# boost_phase.net
KiCad netlist of a schematic drawn in EAGLE
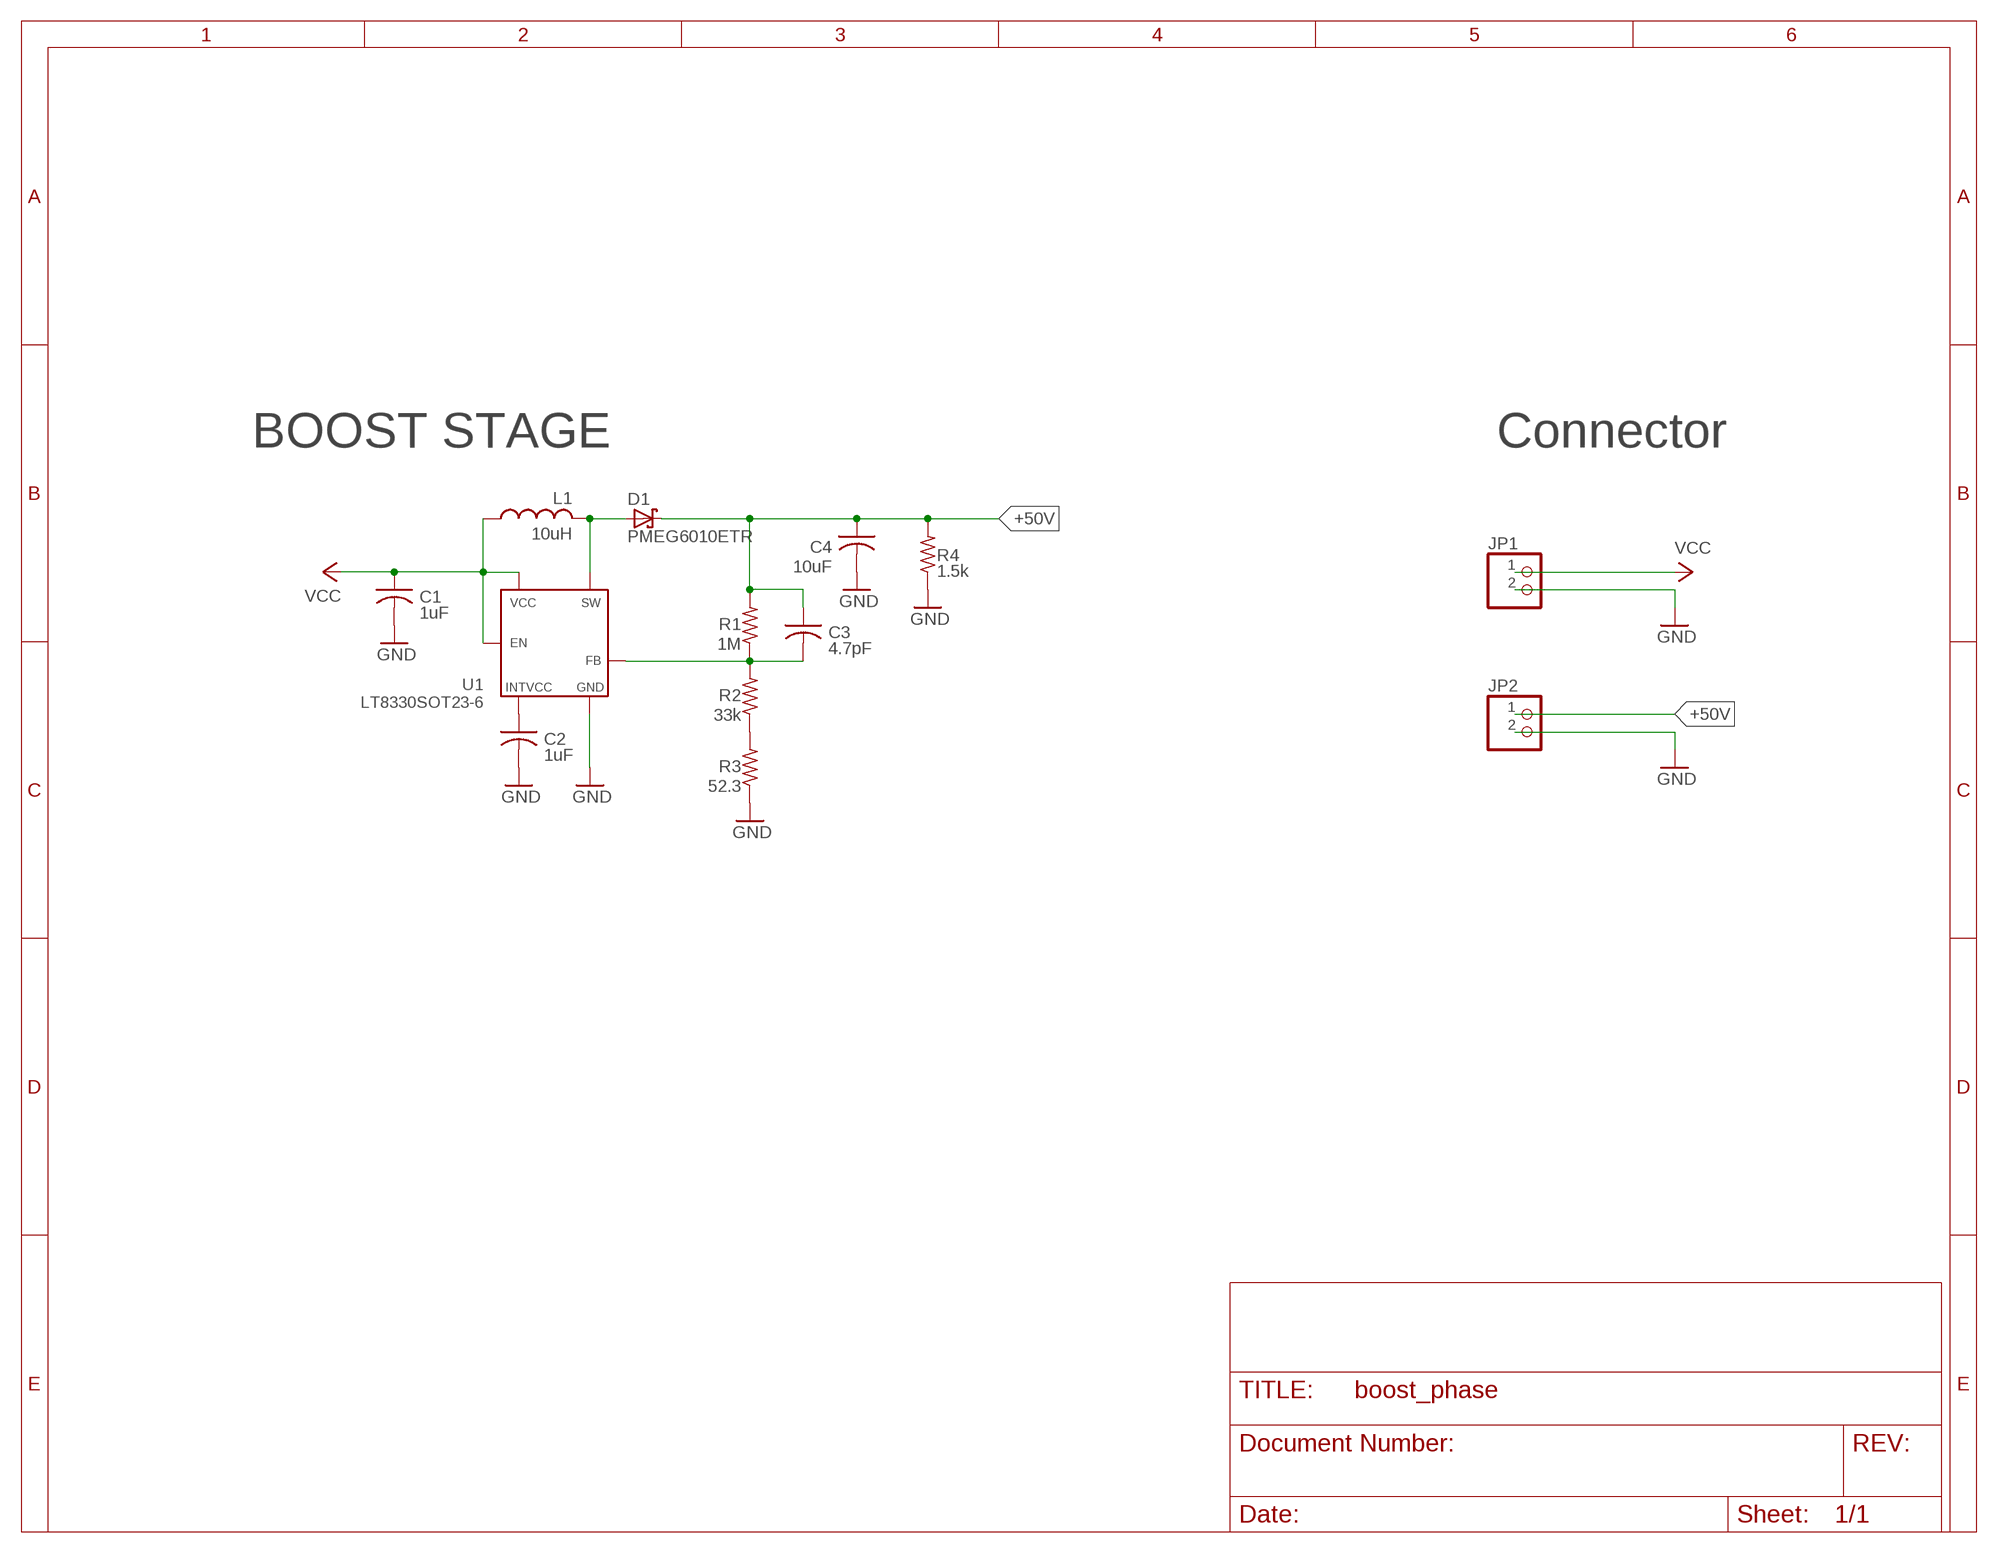
[diagram p0: schematic, sheet 1]

(export (version "E")
  (design (tool "Eeschema 10.0.6"))
  (components
    (comp (ref "C1")
      (value "1uF")
      (footprint "eagle-import:C0805")
      (libsource (lib "eagle-import") (part "C-USC0805"))
    )
    (comp (ref "C2")
      (value "1uF")
      (footprint "eagle-import:C0805")
      (libsource (lib "eagle-import") (part "C-USC0805"))
    )
    (comp (ref "C3")
      (value "4.7pF")
      (footprint "eagle-import:C0805")
      (libsource (lib "eagle-import") (part "C-USC0805"))
    )
    (comp (ref "C4")
      (value "10uF")
      (footprint "eagle-import:2J-LEAD")
      (libsource (lib "eagle-import") (part "CAPACITOR2-J-LEAD"))
    )
    (comp (ref "D1")
      (value "PMEG6010ETR")
      (footprint "eagle-import:SOD123")
      (libsource (lib "eagle-import") (part "SCHOTTKYSOD123"))
    )
    (comp (ref "JP1")
      (value "SCREWTERM_1X2")
      (footprint "eagle-import:SCREWTERM_1X2")
      (libsource (lib "eagle-import") (part "SCREWTERM_1X2"))
    )
    (comp (ref "JP2")
      (value "SCREWTERM_1X2")
      (footprint "eagle-import:SCREWTERM_1X2")
      (libsource (lib "eagle-import") (part "SCREWTERM_1X2"))
    )
    (comp (ref "L1")
      (value "10uH")
      (footprint "eagle-import:PQ2614")
      (libsource (lib "eagle-import") (part "INDUCTORPQ2614"))
    )
    (comp (ref "R1")
      (value "1M")
      (footprint "eagle-import:R0805")
      (libsource (lib "eagle-import") (part "R-US_R0805"))
    )
    (comp (ref "R2")
      (value "33k")
      (footprint "eagle-import:R0805")
      (libsource (lib "eagle-import") (part "R-US_R0805"))
    )
    (comp (ref "R3")
      (value "52.3")
      (footprint "eagle-import:R0805")
      (libsource (lib "eagle-import") (part "R-US_R0805"))
    )
    (comp (ref "R4")
      (value "1.5k")
      (footprint "eagle-import:R2512")
      (libsource (lib "eagle-import") (part "R-US_R2512"))
    )
    (comp (ref "U1")
      (value "LT8330SOT23-6")
      (footprint "eagle-import:SOT23-6")
      (libsource (lib "eagle-import") (part "LT8330SOT23-6"))
    )
  )
  (nets
    (net (code "1") (name "+50V") (class "Default")
      (node (ref "C3") (pin "1") (pinfunction "1_1") (pintype "passive"))
      (node (ref "C4") (pin "P$1") (pinfunction "1_P$1") (pintype "passive"))
      (node (ref "D1") (pin "P$2") (pinfunction "C_P$2") (pintype "passive"))
      (node (ref "JP2") (pin "1") (pinfunction "1_1") (pintype "passive"))
      (node (ref "R1") (pin "2") (pinfunction "2_2") (pintype "passive"))
      (node (ref "R4") (pin "2") (pinfunction "2_2") (pintype "passive"))
    )
    (net (code "2") (name "GND") (class "Default")
      (node (ref "C1") (pin "2") (pinfunction "2_2") (pintype "passive"))
      (node (ref "C2") (pin "2") (pinfunction "2_2") (pintype "passive"))
      (node (ref "C4") (pin "P$2") (pinfunction "2_P$2") (pintype "passive"))
      (node (ref "JP1") (pin "2") (pinfunction "2_2") (pintype "passive"))
      (node (ref "JP2") (pin "2") (pinfunction "2_2") (pintype "passive"))
      (node (ref "R3") (pin "1") (pinfunction "1_1") (pintype "passive"))
      (node (ref "R4") (pin "1") (pinfunction "1_1") (pintype "passive"))
      (node (ref "U1") (pin "2") (pinfunction "GND_2") (pintype "bidirectional"))
    )
    (net (code "3") (name "Net-(D1-A)") (class "Default")
      (node (ref "D1") (pin "P$1") (pinfunction "A_P$1") (pintype "passive"))
      (node (ref "L1") (pin "P$3") (pinfunction "2_P$3") (pintype "passive"))
      (node (ref "U1") (pin "1") (pinfunction "SW_1") (pintype "bidirectional"))
    )
    (net (code "4") (name "Net-(R2-Pad1)") (class "Default")
      (node (ref "R2") (pin "1") (pinfunction "1_1") (pintype "passive"))
      (node (ref "R3") (pin "2") (pinfunction "2_2") (pintype "passive"))
    )
    (net (code "5") (name "Net-(U1-FB)") (class "Default")
      (node (ref "C3") (pin "2") (pinfunction "2_2") (pintype "passive"))
      (node (ref "R1") (pin "1") (pinfunction "1_1") (pintype "passive"))
      (node (ref "R2") (pin "2") (pinfunction "2_2") (pintype "passive"))
      (node (ref "U1") (pin "3") (pinfunction "FB_3") (pintype "bidirectional"))
    )
    (net (code "6") (name "Net-(U1-INTVCC)") (class "Default")
      (node (ref "C2") (pin "1") (pinfunction "1_1") (pintype "passive"))
      (node (ref "U1") (pin "5") (pinfunction "INTVCC_5") (pintype "bidirectional"))
    )
    (net (code "7") (name "VCC") (class "Default")
      (node (ref "C1") (pin "1") (pinfunction "1_1") (pintype "passive"))
      (node (ref "JP1") (pin "1") (pinfunction "1_1") (pintype "passive"))
      (node (ref "L1") (pin "P$2") (pinfunction "1_P$2") (pintype "passive"))
      (node (ref "U1") (pin "4") (pinfunction "EN_4") (pintype "bidirectional"))
      (node (ref "U1") (pin "6") (pinfunction "VCC_6") (pintype "bidirectional"))
    )
  )
)
